# FAIO-Braille.net
KiCad netlist of a schematic drawn in EAGLE
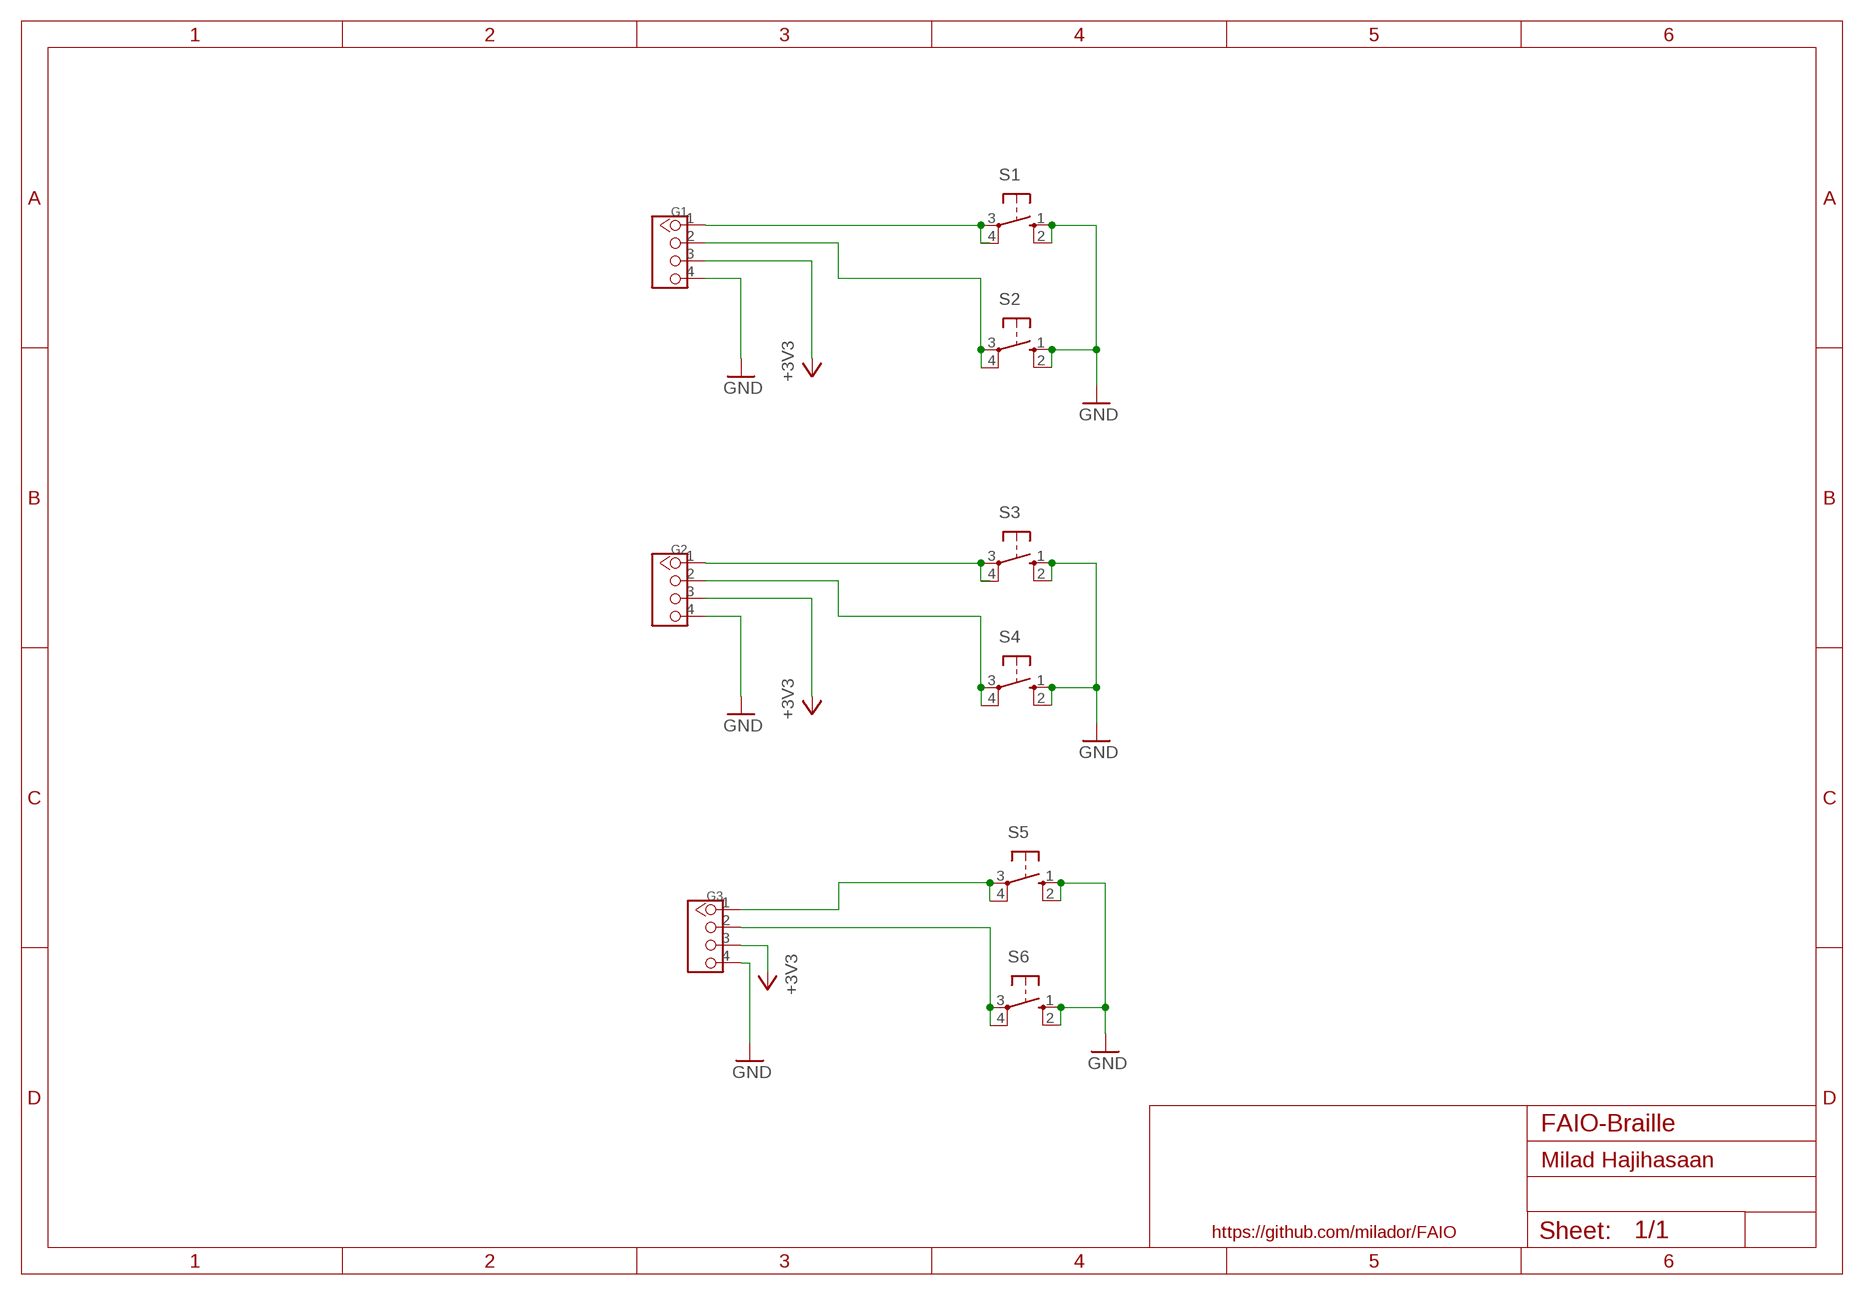
[diagram p0: schematic, sheet 1]

(export (version "E")
  (design (tool "Eeschema 10.0.6"))
  (components
    (comp (ref "G1")
      (value "TWIG-4P-2.0'90D'")
      (footprint "eagle-import:4P-2.0-90D")
      (libsource (lib "eagle-import") (part "TWIG-4P-2.0'90D'"))
    )
    (comp (ref "G2")
      (value "TWIG-4P-2.0'90D'")
      (footprint "eagle-import:4P-2.0-90D")
      (libsource (lib "eagle-import") (part "TWIG-4P-2.0'90D'"))
    )
    (comp (ref "G3")
      (value "TWIG-4P-2.0'90D'")
      (footprint "eagle-import:4P-2.0-90D")
      (libsource (lib "eagle-import") (part "TWIG-4P-2.0'90D'"))
    )
    (comp (ref "S1")
      (value "10-XX")
      (footprint "eagle-import:B3F-10XX")
      (fields (field (name "MPN") "B3F-1000"))
      (libsource (lib "eagle-import") (part "10-XX"))
    )
    (comp (ref "S2")
      (value "10-XX")
      (footprint "eagle-import:B3F-10XX")
      (fields (field (name "MPN") "B3F-1000"))
      (libsource (lib "eagle-import") (part "10-XX"))
    )
    (comp (ref "S3")
      (value "10-XX")
      (footprint "eagle-import:B3F-10XX")
      (fields (field (name "MPN") "B3F-1000"))
      (libsource (lib "eagle-import") (part "10-XX"))
    )
    (comp (ref "S4")
      (value "10-XX")
      (footprint "eagle-import:B3F-10XX")
      (fields (field (name "MPN") "B3F-1000"))
      (libsource (lib "eagle-import") (part "10-XX"))
    )
    (comp (ref "S5")
      (value "10-XX")
      (footprint "eagle-import:B3F-10XX")
      (fields (field (name "MPN") "B3F-1000"))
      (libsource (lib "eagle-import") (part "10-XX"))
    )
    (comp (ref "S6")
      (value "10-XX")
      (footprint "eagle-import:B3F-10XX")
      (fields (field (name "MPN") "B3F-1000"))
      (libsource (lib "eagle-import") (part "10-XX"))
    )
  )
  (nets
    (net (code "1") (name "+3V3") (class "Default")
      (node (ref "G1") (pin "3") (pinfunction "3_3") (pintype "bidirectional"))
      (node (ref "G2") (pin "3") (pinfunction "3_3") (pintype "bidirectional"))
      (node (ref "G3") (pin "3") (pinfunction "3_3") (pintype "bidirectional"))
    )
    (net (code "2") (name "GND") (class "Default")
      (node (ref "G1") (pin "4") (pinfunction "4_4") (pintype "bidirectional"))
      (node (ref "G2") (pin "4") (pinfunction "4_4") (pintype "bidirectional"))
      (node (ref "G3") (pin "4") (pinfunction "4_4") (pintype "bidirectional"))
      (node (ref "S1") (pin "1") (pinfunction "S_1") (pintype "passive"))
      (node (ref "S1") (pin "2") (pinfunction "S1_2") (pintype "passive"))
      (node (ref "S2") (pin "1") (pinfunction "S_1") (pintype "passive"))
      (node (ref "S2") (pin "2") (pinfunction "S1_2") (pintype "passive"))
      (node (ref "S3") (pin "1") (pinfunction "S_1") (pintype "passive"))
      (node (ref "S3") (pin "2") (pinfunction "S1_2") (pintype "passive"))
      (node (ref "S4") (pin "1") (pinfunction "S_1") (pintype "passive"))
      (node (ref "S4") (pin "2") (pinfunction "S1_2") (pintype "passive"))
      (node (ref "S5") (pin "1") (pinfunction "S_1") (pintype "passive"))
      (node (ref "S5") (pin "2") (pinfunction "S1_2") (pintype "passive"))
      (node (ref "S6") (pin "1") (pinfunction "S_1") (pintype "passive"))
      (node (ref "S6") (pin "2") (pinfunction "S1_2") (pintype "passive"))
    )
    (net (code "3") (name "Net-(S1-P)") (class "Default")
      (node (ref "G1") (pin "1") (pinfunction "1_1") (pintype "bidirectional"))
      (node (ref "S1") (pin "3") (pinfunction "P_3") (pintype "passive"))
      (node (ref "S1") (pin "4") (pinfunction "P1_4") (pintype "passive"))
    )
    (net (code "4") (name "Net-(S2-P)") (class "Default")
      (node (ref "G1") (pin "2") (pinfunction "2_2") (pintype "bidirectional"))
      (node (ref "S2") (pin "3") (pinfunction "P_3") (pintype "passive"))
      (node (ref "S2") (pin "4") (pinfunction "P1_4") (pintype "passive"))
    )
    (net (code "5") (name "Net-(S3-P)") (class "Default")
      (node (ref "G2") (pin "1") (pinfunction "1_1") (pintype "bidirectional"))
      (node (ref "S3") (pin "3") (pinfunction "P_3") (pintype "passive"))
      (node (ref "S3") (pin "4") (pinfunction "P1_4") (pintype "passive"))
    )
    (net (code "6") (name "Net-(S4-P)") (class "Default")
      (node (ref "G2") (pin "2") (pinfunction "2_2") (pintype "bidirectional"))
      (node (ref "S4") (pin "3") (pinfunction "P_3") (pintype "passive"))
      (node (ref "S4") (pin "4") (pinfunction "P1_4") (pintype "passive"))
    )
    (net (code "7") (name "Net-(S5-P)") (class "Default")
      (node (ref "G3") (pin "1") (pinfunction "1_1") (pintype "bidirectional"))
      (node (ref "S5") (pin "3") (pinfunction "P_3") (pintype "passive"))
      (node (ref "S5") (pin "4") (pinfunction "P1_4") (pintype "passive"))
    )
    (net (code "8") (name "Net-(S6-P)") (class "Default")
      (node (ref "G3") (pin "2") (pinfunction "2_2") (pintype "bidirectional"))
      (node (ref "S6") (pin "3") (pinfunction "P_3") (pintype "passive"))
      (node (ref "S6") (pin "4") (pinfunction "P1_4") (pintype "passive"))
    )
  )
)
